# LED_sign_board_3.net
KiCad netlist of a schematic drawn in EAGLE
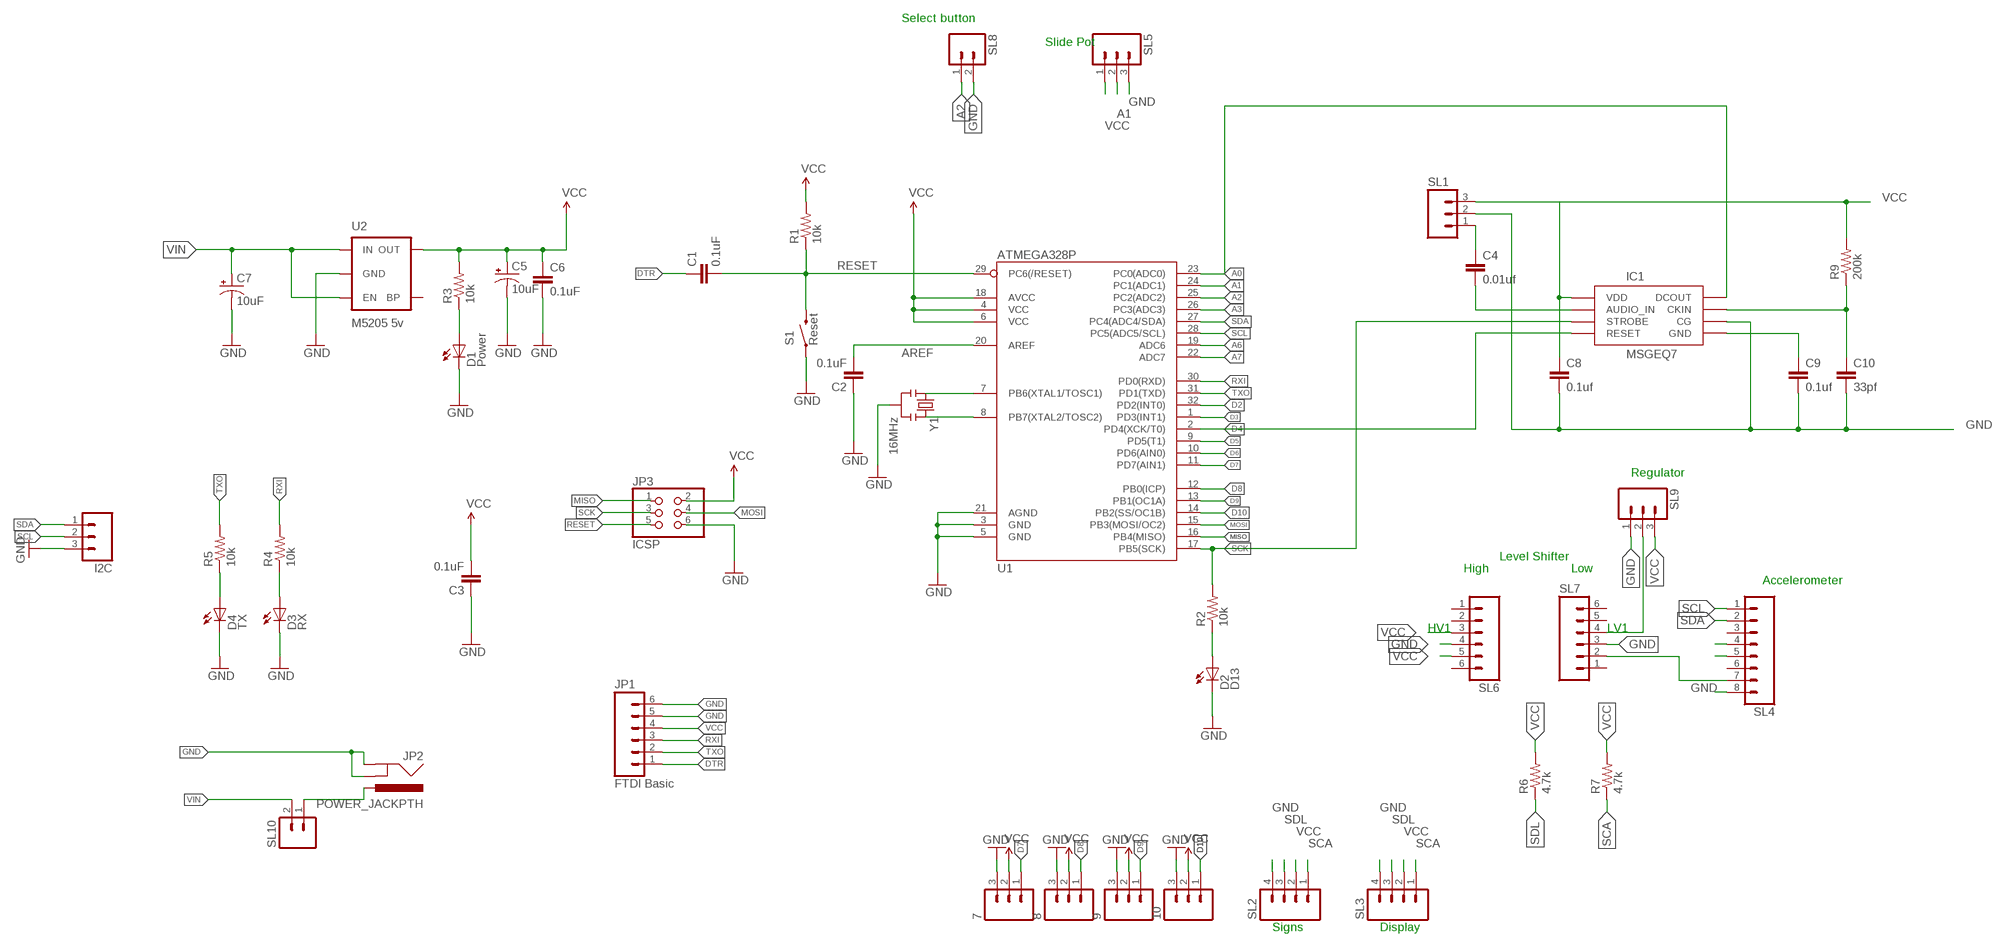
[diagram p0: schematic, sheet 1]

(export (version "E")
  (design (tool "Eeschema 10.0.6"))
  (components
    (comp (ref "7")
      (value "M03PTH")
      (footprint "eagle-import:1X03")
      (libsource (lib "eagle-import") (part "M03PTH"))
    )
    (comp (ref "8")
      (value "M03PTH")
      (footprint "eagle-import:1X03")
      (libsource (lib "eagle-import") (part "M03PTH"))
    )
    (comp (ref "9")
      (value "M03PTH")
      (footprint "eagle-import:1X03")
      (libsource (lib "eagle-import") (part "M03PTH"))
    )
    (comp (ref "10")
      (value "M03PTH")
      (footprint "eagle-import:1X03")
      (libsource (lib "eagle-import") (part "M03PTH"))
    )
    (comp (ref "C1")
      (value "0.1uF")
      (footprint "eagle-import:0603-CAP")
      (libsource (lib "eagle-import") (part "CAP0603-CAP"))
    )
    (comp (ref "C2")
      (value "0.1uF")
      (footprint "eagle-import:0603-CAP")
      (libsource (lib "eagle-import") (part "CAP0603-CAP"))
    )
    (comp (ref "C3")
      (value "0.1uF")
      (footprint "eagle-import:0603-CAP")
      (libsource (lib "eagle-import") (part "CAP0603-CAP"))
    )
    (comp (ref "C4")
      (value "0.01uf")
      (footprint "eagle-import:C2.5-3")
      (libsource (lib "eagle-import") (part "C2,5-3"))
    )
    (comp (ref "C5")
      (value "10uF")
      (footprint "eagle-import:EIA3216")
      (libsource (lib "eagle-import") (part "CAP_POL1206"))
    )
    (comp (ref "C6")
      (value "0.1uF")
      (footprint "eagle-import:0603-CAP")
      (libsource (lib "eagle-import") (part "CAP0603-CAP"))
    )
    (comp (ref "C7")
      (value "10uF")
      (footprint "eagle-import:EIA3216")
      (libsource (lib "eagle-import") (part "CAP_POL1206"))
    )
    (comp (ref "C8")
      (value "0.1uf")
      (footprint "eagle-import:C2.5-3")
      (libsource (lib "eagle-import") (part "C2,5-3"))
    )
    (comp (ref "C9")
      (value "0.1uf")
      (footprint "eagle-import:C2.5-3")
      (libsource (lib "eagle-import") (part "C2,5-3"))
    )
    (comp (ref "C10")
      (value "33pf")
      (footprint "eagle-import:C2.5-3")
      (libsource (lib "eagle-import") (part "C2,5-3"))
    )
    (comp (ref "D1")
      (value "Power")
      (footprint "eagle-import:LED-0603")
      (libsource (lib "eagle-import") (part "LED-RED0603"))
    )
    (comp (ref "D2")
      (value "D13")
      (footprint "eagle-import:LED-0603")
      (libsource (lib "eagle-import") (part "LED-RED0603"))
    )
    (comp (ref "D3")
      (value "RX")
      (footprint "eagle-import:LED-0603")
      (libsource (lib "eagle-import") (part "LED-GREEN0603"))
    )
    (comp (ref "D4")
      (value "TX")
      (footprint "eagle-import:LED-0603")
      (libsource (lib "eagle-import") (part "LED-RED0603"))
    )
    (comp (ref "I2C")
      (value "M03PTH")
      (footprint "eagle-import:1X03")
      (libsource (lib "eagle-import") (part "M03PTH"))
    )
    (comp (ref "IC1")
      (value "MSGEQ7DIL")
      (footprint "eagle-import:DIL-08")
      (libsource (lib "eagle-import") (part "MSGEQ7DIL"))
    )
    (comp (ref "JP1")
      (value "FTDI Basic")
      (footprint "eagle-import:1X06")
      (libsource (lib "eagle-import") (part "M06SIP"))
    )
    (comp (ref "JP2")
      (value "POWER_JACKPTH")
      (footprint "eagle-import:POWER_JACK_PTH")
      (libsource (lib "eagle-import") (part "POWER_JACKPTH"))
    )
    (comp (ref "JP3")
      (value "ICSP")
      (footprint "eagle-import:2X03")
      (libsource (lib "eagle-import") (part "PINHD-2X3"))
    )
    (comp (ref "R1")
      (value "10k")
      (footprint "eagle-import:0603-RES")
      (libsource (lib "eagle-import") (part "RESISTOR0603-RES"))
    )
    (comp (ref "R2")
      (value "10k")
      (footprint "eagle-import:0603-RES")
      (libsource (lib "eagle-import") (part "RESISTOR0603-RES"))
    )
    (comp (ref "R3")
      (value "10k")
      (footprint "eagle-import:0603-RES")
      (libsource (lib "eagle-import") (part "RESISTOR0603-RES"))
    )
    (comp (ref "R4")
      (value "10k")
      (footprint "eagle-import:0603-RES")
      (libsource (lib "eagle-import") (part "RESISTOR0603-RES"))
    )
    (comp (ref "R5")
      (value "10k")
      (footprint "eagle-import:0603-RES")
      (libsource (lib "eagle-import") (part "RESISTOR0603-RES"))
    )
    (comp (ref "R6")
      (value "4.7k")
      (footprint "eagle-import:1206")
      (libsource (lib "eagle-import") (part "SparkFun-Resistors_RESISTOR1206"))
    )
    (comp (ref "R7")
      (value "4.7k")
      (footprint "eagle-import:1206")
      (libsource (lib "eagle-import") (part "SparkFun-Resistors_RESISTOR1206"))
    )
    (comp (ref "R9")
      (value "200k")
      (footprint "eagle-import:1206")
      (libsource (lib "eagle-import") (part "SparkFun-Resistors_RESISTOR1206"))
    )
    (comp (ref "S1")
      (value "Reset")
      (footprint "eagle-import:TACTILE_SWITCH_SMD")
      (libsource (lib "eagle-import") (part "SWITCH-MOMENTARY-2SMD"))
    )
    (comp (ref "SL1")
      (value "M03")
      (footprint "eagle-import:03P")
      (libsource (lib "eagle-import") (part "M03"))
    )
    (comp (ref "SL2")
      (value "M04")
      (footprint "eagle-import:04P")
      (libsource (lib "eagle-import") (part "M04"))
    )
    (comp (ref "SL3")
      (value "M04")
      (footprint "eagle-import:04P")
      (libsource (lib "eagle-import") (part "M04"))
    )
    (comp (ref "SL4")
      (value "M08")
      (footprint "eagle-import:08P")
      (libsource (lib "eagle-import") (part "M08"))
    )
    (comp (ref "SL5")
      (value "M03")
      (footprint "eagle-import:03P")
      (libsource (lib "eagle-import") (part "M03"))
    )
    (comp (ref "SL6")
      (value "M06")
      (footprint "eagle-import:06P")
      (libsource (lib "eagle-import") (part "M06"))
    )
    (comp (ref "SL7")
      (value "M06")
      (footprint "eagle-import:06P")
      (libsource (lib "eagle-import") (part "M06"))
    )
    (comp (ref "SL8")
      (value "M02")
      (footprint "eagle-import:02P")
      (libsource (lib "eagle-import") (part "M02"))
    )
    (comp (ref "SL9")
      (value "M03")
      (footprint "eagle-import:03P")
      (libsource (lib "eagle-import") (part "M03"))
    )
    (comp (ref "SL10")
      (value "M02")
      (footprint "eagle-import:02P")
      (libsource (lib "eagle-import") (part "M02"))
    )
    (comp (ref "U1")
      (value "ATMEGA328P")
      (footprint "eagle-import:TQFP32-08")
      (libsource (lib "eagle-import") (part "ATMEGA328_SMT"))
    )
    (comp (ref "U2")
      (value "M5205 5v")
      (footprint "eagle-import:SOT23-5")
      (libsource (lib "eagle-import") (part "MIC52055V"))
    )
    (comp (ref "Y1")
      (value "16MHz")
      (footprint "eagle-import:RESONATOR-SMD")
      (libsource (lib "eagle-import") (part "RESONATOR16MHZ"))
    )
  )
  (nets
    (net (code "1") (name "/AREF") (class "Default")
      (node (ref "C2") (pin "2") (pinfunction "2_2") (pintype "passive"))
      (node (ref "U1") (pin "20") (pinfunction "AREF_20") (pintype "bidirectional"))
    )
    (net (code "2") (name "A0") (class "Default")
      (node (ref "IC1") (pin "3") (pinfunction "DCOUT_3") (pintype "bidirectional"))
      (node (ref "U1") (pin "23") (pinfunction "PC0(ADC0)_23") (pintype "bidirectional"))
    )
    (net (code "3") (name "A1") (class "Default")
      (node (ref "SL5") (pin "2") (pinfunction "2_2") (pintype "passive"))
      (node (ref "U1") (pin "24") (pinfunction "PC1(ADC1)_24") (pintype "bidirectional"))
    )
    (net (code "4") (name "A2") (class "Default")
      (node (ref "SL8") (pin "1") (pinfunction "1_1") (pintype "passive"))
      (node (ref "U1") (pin "25") (pinfunction "PC2(ADC2)_25") (pintype "bidirectional"))
    )
    (net (code "5") (name "A3") (class "Default")
      (node (ref "U1") (pin "26") (pinfunction "PC3(ADC3)_26") (pintype "bidirectional"))
    )
    (net (code "6") (name "A6") (class "Default")
      (node (ref "U1") (pin "19") (pinfunction "ADC6_19") (pintype "bidirectional"))
    )
    (net (code "7") (name "A7") (class "Default")
      (node (ref "U1") (pin "22") (pinfunction "ADC7_22") (pintype "bidirectional"))
    )
    (net (code "8") (name "D2") (class "Default")
      (node (ref "U1") (pin "32") (pinfunction "PD2(INT0)_32") (pintype "bidirectional"))
    )
    (net (code "9") (name "D3") (class "Default")
      (node (ref "U1") (pin "1") (pinfunction "PD3(INT1)_1") (pintype "bidirectional"))
    )
    (net (code "10") (name "D4") (class "Default")
      (node (ref "IC1") (pin "7") (pinfunction "RESET_7") (pintype "input"))
      (node (ref "U1") (pin "2") (pinfunction "PD4(XCK/T0)_2") (pintype "bidirectional"))
    )
    (net (code "11") (name "D5") (class "Default")
      (node (ref "U1") (pin "9") (pinfunction "PD5(T1)_9") (pintype "bidirectional"))
    )
    (net (code "12") (name "D6") (class "Default")
      (node (ref "U1") (pin "10") (pinfunction "PD6(AIN0)_10") (pintype "bidirectional"))
    )
    (net (code "13") (name "D7") (class "Default")
      (node (ref "7") (pin "1") (pinfunction "1_1") (pintype "passive"))
      (node (ref "U1") (pin "11") (pinfunction "PD7(AIN1)_11") (pintype "bidirectional"))
    )
    (net (code "14") (name "D8") (class "Default")
      (node (ref "8") (pin "1") (pinfunction "1_1") (pintype "passive"))
      (node (ref "U1") (pin "12") (pinfunction "PB0(ICP)_12") (pintype "bidirectional"))
    )
    (net (code "15") (name "D9") (class "Default")
      (node (ref "9") (pin "1") (pinfunction "1_1") (pintype "passive"))
      (node (ref "U1") (pin "13") (pinfunction "PB1(OC1A)_13") (pintype "bidirectional"))
    )
    (net (code "16") (name "D10") (class "Default")
      (node (ref "10") (pin "1") (pinfunction "1_1") (pintype "passive"))
      (node (ref "U1") (pin "14") (pinfunction "PB2(SS/OC1B)_14") (pintype "bidirectional"))
    )
    (net (code "17") (name "DTR") (class "Default")
      (node (ref "C1") (pin "1") (pinfunction "1_1") (pintype "passive"))
      (node (ref "JP1") (pin "1") (pinfunction "1_1") (pintype "passive"))
    )
    (net (code "18") (name "GND") (class "Default")
      (node (ref "10") (pin "3") (pinfunction "3_3") (pintype "passive"))
      (node (ref "7") (pin "3") (pinfunction "3_3") (pintype "passive"))
      (node (ref "8") (pin "3") (pinfunction "3_3") (pintype "passive"))
      (node (ref "9") (pin "3") (pinfunction "3_3") (pintype "passive"))
      (node (ref "C10") (pin "2") (pinfunction "2_2") (pintype "passive"))
      (node (ref "C2") (pin "1") (pinfunction "1_1") (pintype "passive"))
      (node (ref "C3") (pin "1") (pinfunction "1_1") (pintype "passive"))
      (node (ref "C5") (pin "C") (pinfunction "-_C") (pintype "passive"))
      (node (ref "C6") (pin "2") (pinfunction "2_2") (pintype "passive"))
      (node (ref "C7") (pin "C") (pinfunction "-_C") (pintype "passive"))
      (node (ref "C8") (pin "2") (pinfunction "2_2") (pintype "passive"))
      (node (ref "C9") (pin "2") (pinfunction "2_2") (pintype "passive"))
      (node (ref "D1") (pin "C") (pinfunction "C_C") (pintype "passive"))
      (node (ref "D2") (pin "C") (pinfunction "C_C") (pintype "passive"))
      (node (ref "D3") (pin "C") (pinfunction "C_C") (pintype "passive"))
      (node (ref "D4") (pin "C") (pinfunction "C_C") (pintype "passive"))
      (node (ref "I2C") (pin "3") (pinfunction "3_3") (pintype "passive"))
      (node (ref "IC1") (pin "6") (pinfunction "CG_6") (pintype "bidirectional"))
      (node (ref "JP1") (pin "5") (pinfunction "5_5") (pintype "passive"))
      (node (ref "JP1") (pin "6") (pinfunction "6_6") (pintype "passive"))
      (node (ref "JP2") (pin "GND") (pinfunction "GND_GND") (pintype "bidirectional"))
      (node (ref "JP2") (pin "GNDBREAK") (pinfunction "GNDBREAK_GNDBREAK") (pintype "bidirectional"))
      (node (ref "JP3") (pin "6") (pinfunction "6_6") (pintype "passive"))
      (node (ref "S1") (pin "1") (pinfunction "1_1") (pintype "passive"))
      (node (ref "SL1") (pin "2") (pinfunction "2_2") (pintype "passive"))
      (node (ref "SL2") (pin "4") (pinfunction "4_4") (pintype "passive"))
      (node (ref "SL3") (pin "4") (pinfunction "4_4") (pintype "passive"))
      (node (ref "SL4") (pin "8") (pinfunction "8_8") (pintype "passive"))
      (node (ref "SL5") (pin "3") (pinfunction "3_3") (pintype "passive"))
      (node (ref "SL6") (pin "4") (pinfunction "4_4") (pintype "passive"))
      (node (ref "SL7") (pin "3") (pinfunction "3_3") (pintype "passive"))
      (node (ref "SL7") (pin "4") (pinfunction "4_4") (pintype "passive"))
      (node (ref "SL8") (pin "2") (pinfunction "2_2") (pintype "passive"))
      (node (ref "SL9") (pin "1") (pinfunction "1_1") (pintype "passive"))
      (node (ref "SL9") (pin "2") (pinfunction "2_2") (pintype "passive"))
      (node (ref "U1") (pin "21") (pinfunction "AGND_21") (pintype "bidirectional"))
      (node (ref "U1") (pin "3") (pinfunction "GND_3") (pintype "bidirectional"))
      (node (ref "U1") (pin "5") (pinfunction "GND_5") (pintype "bidirectional"))
      (node (ref "U2") (pin "2") (pinfunction "GND_2") (pintype "input"))
      (node (ref "Y1") (pin "2") (pinfunction "2_2") (pintype "passive"))
    )
    (net (code "19") (name "MISO") (class "Default")
      (node (ref "JP3") (pin "1") (pinfunction "1_1") (pintype "passive"))
      (node (ref "U1") (pin "16") (pinfunction "PB4(MISO)_16") (pintype "bidirectional"))
    )
    (net (code "20") (name "MOSI") (class "Default")
      (node (ref "JP3") (pin "4") (pinfunction "4_4") (pintype "passive"))
      (node (ref "U1") (pin "15") (pinfunction "PB3(MOSI/OC2)_15") (pintype "bidirectional"))
    )
    (net (code "21") (name "Net-(C4-Pad1)") (class "Default")
      (node (ref "C4") (pin "1") (pinfunction "1_1") (pintype "passive"))
      (node (ref "SL1") (pin "1") (pinfunction "1_1") (pintype "passive"))
    )
    (net (code "22") (name "Net-(D1-PadA)") (class "Default")
      (node (ref "D1") (pin "A") (pinfunction "A_A") (pintype "passive"))
      (node (ref "R3") (pin "1") (pinfunction "1_1") (pintype "passive"))
    )
    (net (code "23") (name "Net-(D2-PadA)") (class "Default")
      (node (ref "D2") (pin "A") (pinfunction "A_A") (pintype "passive"))
      (node (ref "R2") (pin "1") (pinfunction "1_1") (pintype "passive"))
    )
    (net (code "24") (name "Net-(D3-PadA)") (class "Default")
      (node (ref "D3") (pin "A") (pinfunction "A_A") (pintype "passive"))
      (node (ref "R4") (pin "1") (pinfunction "1_1") (pintype "passive"))
    )
    (net (code "25") (name "Net-(D4-PadA)") (class "Default")
      (node (ref "D4") (pin "A") (pinfunction "A_A") (pintype "passive"))
      (node (ref "R5") (pin "1") (pinfunction "1_1") (pintype "passive"))
    )
    (net (code "26") (name "Net-(IC1-AUDIO_IN)") (class "Default")
      (node (ref "C4") (pin "2") (pinfunction "2_2") (pintype "passive"))
      (node (ref "IC1") (pin "5") (pinfunction "AUDIO_IN_5") (pintype "input"))
    )
    (net (code "27") (name "Net-(IC1-CKIN)") (class "Default")
      (node (ref "C10") (pin "1") (pinfunction "1_1") (pintype "passive"))
      (node (ref "IC1") (pin "8") (pinfunction "CKIN_8") (pintype "bidirectional"))
      (node (ref "R9") (pin "1") (pinfunction "1_1") (pintype "passive"))
    )
    (net (code "28") (name "Net-(IC1-GND)") (class "Default")
      (node (ref "C9") (pin "1") (pinfunction "1_1") (pintype "passive"))
      (node (ref "IC1") (pin "2") (pinfunction "GND_2") (pintype "bidirectional"))
    )
    (net (code "29") (name "Net-(JP2-PadPWR)") (class "Default")
      (node (ref "JP2") (pin "PWR") (pinfunction "PWR_PWR") (pintype "bidirectional"))
      (node (ref "SL10") (pin "1") (pinfunction "1_1") (pintype "passive"))
    )
    (net (code "30") (name "Net-(SL4-Pad7)") (class "Default")
      (node (ref "SL4") (pin "7") (pinfunction "7_7") (pintype "passive"))
      (node (ref "SL7") (pin "2") (pinfunction "2_2") (pintype "passive"))
    )
    (net (code "31") (name "Net-(U1-PB6(XTAL1{slash}TOSC1))") (class "Default")
      (node (ref "U1") (pin "7") (pinfunction "PB6(XTAL1/TOSC1)_7") (pintype "bidirectional"))
      (node (ref "Y1") (pin "1") (pinfunction "1_1") (pintype "passive"))
    )
    (net (code "32") (name "Net-(U1-PB7(XTAL2{slash}TOSC2))") (class "Default")
      (node (ref "U1") (pin "8") (pinfunction "PB7(XTAL2/TOSC2)_8") (pintype "bidirectional"))
      (node (ref "Y1") (pin "3") (pinfunction "3_3") (pintype "passive"))
    )
    (net (code "33") (name "RESET") (class "Default")
      (node (ref "C1") (pin "2") (pinfunction "2_2") (pintype "passive"))
      (node (ref "JP3") (pin "5") (pinfunction "5_5") (pintype "passive"))
      (node (ref "R1") (pin "1") (pinfunction "1_1") (pintype "passive"))
      (node (ref "S1") (pin "3") (pinfunction "2_3") (pintype "passive"))
      (node (ref "U1") (pin "29") (pinfunction "PC6(/RESET)_29") (pintype "bidirectional"))
    )
    (net (code "34") (name "RXI") (class "Default")
      (node (ref "JP1") (pin "3") (pinfunction "3_3") (pintype "passive"))
      (node (ref "R4") (pin "2") (pinfunction "2_2") (pintype "passive"))
      (node (ref "U1") (pin "30") (pinfunction "PD0(RXD)_30") (pintype "bidirectional"))
    )
    (net (code "35") (name "SCA") (class "Default")
      (node (ref "R7") (pin "1") (pinfunction "1_1") (pintype "passive"))
      (node (ref "SL2") (pin "1") (pinfunction "1_1") (pintype "passive"))
      (node (ref "SL3") (pin "1") (pinfunction "1_1") (pintype "passive"))
    )
    (net (code "36") (name "SCK") (class "Default")
      (node (ref "IC1") (pin "4") (pinfunction "STROBE_4") (pintype "input"))
      (node (ref "JP3") (pin "3") (pinfunction "3_3") (pintype "passive"))
      (node (ref "R2") (pin "2") (pinfunction "2_2") (pintype "passive"))
      (node (ref "U1") (pin "17") (pinfunction "PB5(SCK)_17") (pintype "bidirectional"))
    )
    (net (code "37") (name "SCL") (class "Default")
      (node (ref "I2C") (pin "2") (pinfunction "2_2") (pintype "passive"))
      (node (ref "SL4") (pin "1") (pinfunction "1_1") (pintype "passive"))
      (node (ref "U1") (pin "28") (pinfunction "PC5(ADC5/SCL)_28") (pintype "bidirectional"))
    )
    (net (code "38") (name "SDA") (class "Default")
      (node (ref "I2C") (pin "1") (pinfunction "1_1") (pintype "passive"))
      (node (ref "SL4") (pin "2") (pinfunction "2_2") (pintype "passive"))
      (node (ref "U1") (pin "27") (pinfunction "PC4(ADC4/SDA)_27") (pintype "bidirectional"))
    )
    (net (code "39") (name "SDL") (class "Default")
      (node (ref "R6") (pin "1") (pinfunction "1_1") (pintype "passive"))
      (node (ref "SL2") (pin "3") (pinfunction "3_3") (pintype "passive"))
      (node (ref "SL3") (pin "3") (pinfunction "3_3") (pintype "passive"))
    )
    (net (code "40") (name "TXO") (class "Default")
      (node (ref "JP1") (pin "2") (pinfunction "2_2") (pintype "passive"))
      (node (ref "R5") (pin "2") (pinfunction "2_2") (pintype "passive"))
      (node (ref "U1") (pin "31") (pinfunction "PD1(TXD)_31") (pintype "bidirectional"))
    )
    (net (code "41") (name "VCC") (class "Default")
      (node (ref "10") (pin "2") (pinfunction "2_2") (pintype "passive"))
      (node (ref "7") (pin "2") (pinfunction "2_2") (pintype "passive"))
      (node (ref "8") (pin "2") (pinfunction "2_2") (pintype "passive"))
      (node (ref "9") (pin "2") (pinfunction "2_2") (pintype "passive"))
      (node (ref "C3") (pin "2") (pinfunction "2_2") (pintype "passive"))
      (node (ref "C5") (pin "A") (pinfunction "+_A") (pintype "passive"))
      (node (ref "C6") (pin "1") (pinfunction "1_1") (pintype "passive"))
      (node (ref "C8") (pin "1") (pinfunction "1_1") (pintype "passive"))
      (node (ref "IC1") (pin "1") (pinfunction "VDD_1") (pintype "input"))
      (node (ref "JP1") (pin "4") (pinfunction "4_4") (pintype "passive"))
      (node (ref "JP3") (pin "2") (pinfunction "2_2") (pintype "passive"))
      (node (ref "R1") (pin "2") (pinfunction "2_2") (pintype "passive"))
      (node (ref "R3") (pin "2") (pinfunction "2_2") (pintype "passive"))
      (node (ref "R6") (pin "2") (pinfunction "2_2") (pintype "passive"))
      (node (ref "R7") (pin "2") (pinfunction "2_2") (pintype "passive"))
      (node (ref "R9") (pin "2") (pinfunction "2_2") (pintype "passive"))
      (node (ref "SL1") (pin "3") (pinfunction "3_3") (pintype "passive"))
      (node (ref "SL2") (pin "2") (pinfunction "2_2") (pintype "passive"))
      (node (ref "SL3") (pin "2") (pinfunction "2_2") (pintype "passive"))
      (node (ref "SL5") (pin "1") (pinfunction "1_1") (pintype "passive"))
      (node (ref "SL6") (pin "3") (pinfunction "3_3") (pintype "passive"))
      (node (ref "SL6") (pin "5") (pinfunction "5_5") (pintype "passive"))
      (node (ref "SL9") (pin "3") (pinfunction "3_3") (pintype "passive"))
      (node (ref "U1") (pin "18") (pinfunction "AVCC_18") (pintype "bidirectional"))
      (node (ref "U1") (pin "4") (pinfunction "VCC_4") (pintype "bidirectional"))
      (node (ref "U1") (pin "6") (pinfunction "VCC_6") (pintype "bidirectional"))
      (node (ref "U2") (pin "5") (pinfunction "OUT_5") (pintype "passive"))
    )
    (net (code "42") (name "VIN") (class "Default")
      (node (ref "C7") (pin "A") (pinfunction "+_A") (pintype "passive"))
      (node (ref "SL10") (pin "2") (pinfunction "2_2") (pintype "passive"))
      (node (ref "U2") (pin "1") (pinfunction "IN_1") (pintype "input"))
      (node (ref "U2") (pin "3") (pinfunction "EN_3") (pintype "input"))
    )
    (net (code "43") (name "unconnected-(SL4-Pad3)") (class "Default")
      (node (ref "SL4") (pin "3") (pinfunction "3_3") (pintype "passive"))
    )
    (net (code "44") (name "unconnected-(SL4-Pad4)") (class "Default")
      (node (ref "SL4") (pin "4") (pinfunction "4_4") (pintype "passive"))
    )
    (net (code "45") (name "unconnected-(SL4-Pad5)") (class "Default")
      (node (ref "SL4") (pin "5") (pinfunction "5_5") (pintype "passive"))
    )
    (net (code "46") (name "unconnected-(SL4-Pad6)") (class "Default")
      (node (ref "SL4") (pin "6") (pinfunction "6_6") (pintype "passive"))
    )
    (net (code "47") (name "unconnected-(SL6-Pad1)") (class "Default")
      (node (ref "SL6") (pin "1") (pinfunction "1_1") (pintype "passive"))
    )
    (net (code "48") (name "unconnected-(SL6-Pad2)") (class "Default")
      (node (ref "SL6") (pin "2") (pinfunction "2_2") (pintype "passive"))
    )
    (net (code "49") (name "unconnected-(SL6-Pad6)") (class "Default")
      (node (ref "SL6") (pin "6") (pinfunction "6_6") (pintype "passive"))
    )
    (net (code "50") (name "unconnected-(SL7-Pad1)") (class "Default")
      (node (ref "SL7") (pin "1") (pinfunction "1_1") (pintype "passive"))
    )
    (net (code "51") (name "unconnected-(SL7-Pad5)") (class "Default")
      (node (ref "SL7") (pin "5") (pinfunction "5_5") (pintype "passive"))
    )
    (net (code "52") (name "unconnected-(SL7-Pad6)") (class "Default")
      (node (ref "SL7") (pin "6") (pinfunction "6_6") (pintype "passive"))
    )
    (net (code "53") (name "unconnected-(U2-BP-Pad4)") (class "Default")
      (node (ref "U2") (pin "4") (pinfunction "BP_4") (pintype "input"))
    )
  )
)
